# MegaShield.net
KiCad netlist of a schematic drawn in EAGLE
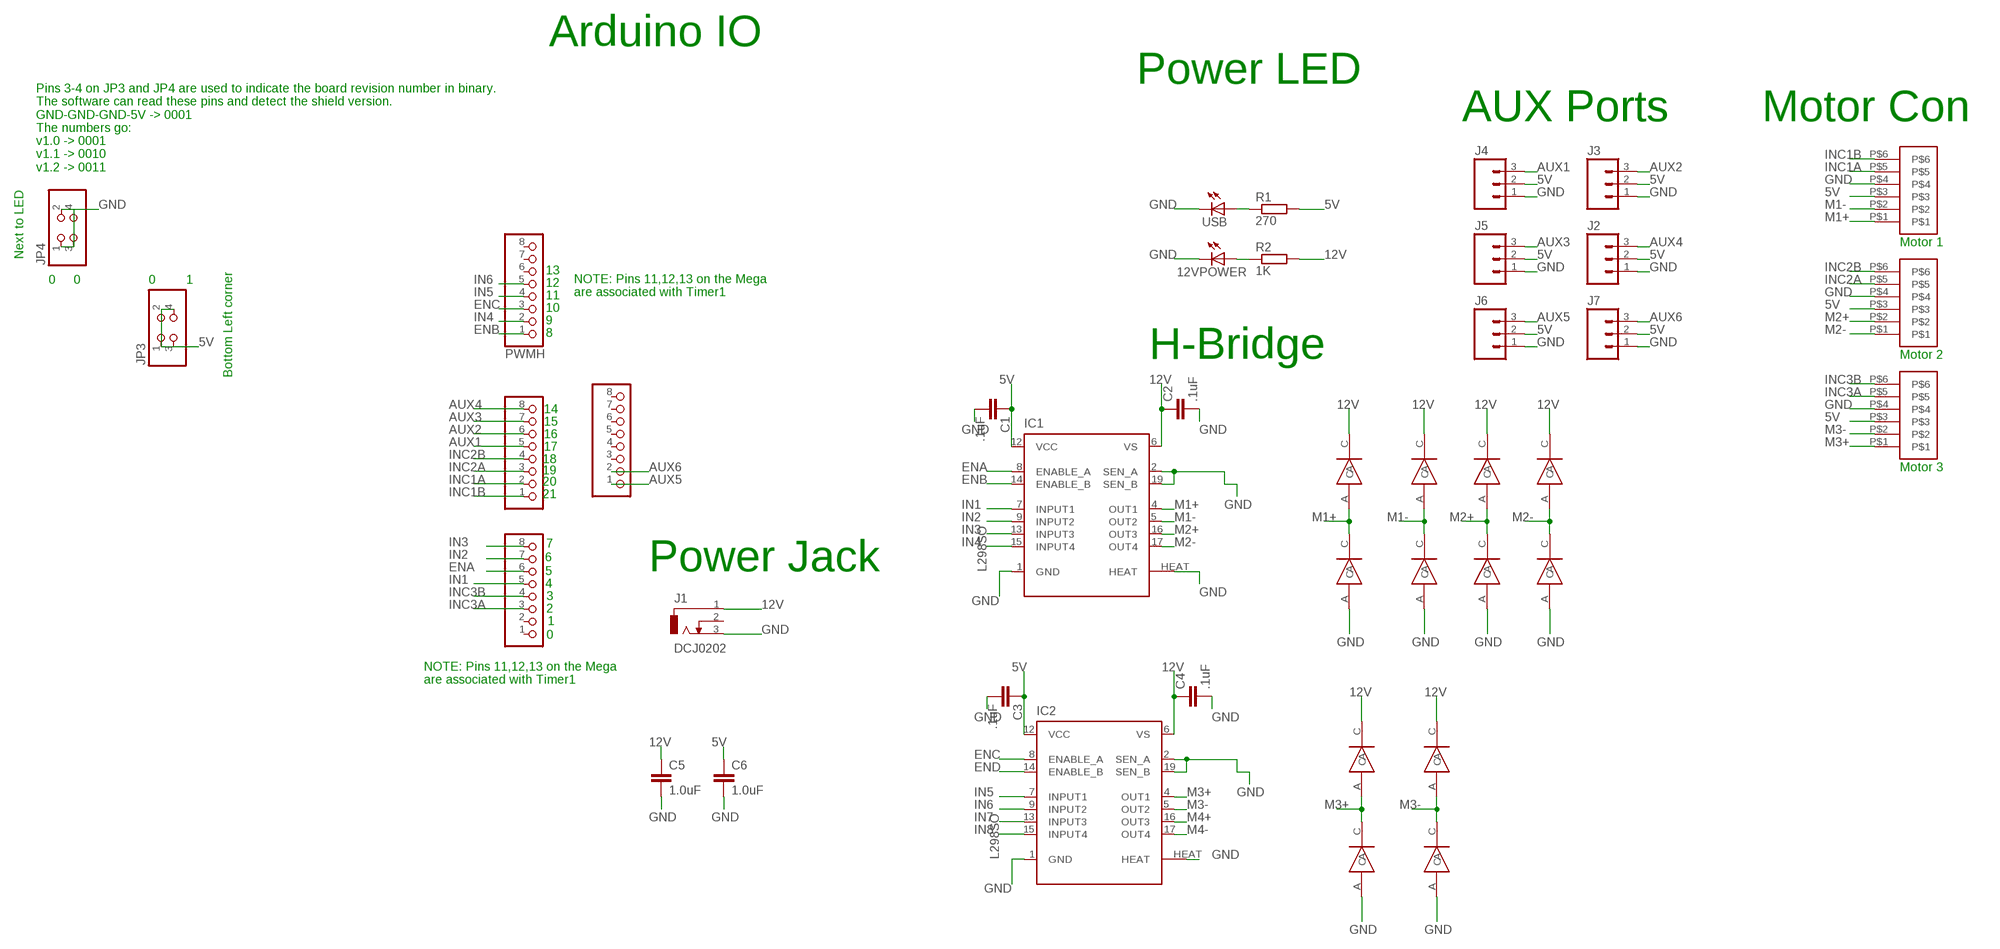
[diagram p0: schematic, sheet 1]

(export (version "E")
  (design (tool "Eeschema 10.0.6"))
  (components
    (comp (ref "12VPOWER")
      (value "LED_E")
      (footprint "eagle-import:LED_1206")
      (libsource (lib "eagle-import") (part "LED_E"))
    )
    (comp (ref "C1")
      (value ".1uF")
      (footprint "eagle-import:C0805")
      (libsource (lib "eagle-import") (part "C"))
    )
    (comp (ref "C2")
      (value ".1uF")
      (footprint "eagle-import:C0805")
      (libsource (lib "eagle-import") (part "C"))
    )
    (comp (ref "C3")
      (value ".1uF")
      (footprint "eagle-import:C0805")
      (libsource (lib "eagle-import") (part "C"))
    )
    (comp (ref "C4")
      (value ".1uF")
      (footprint "eagle-import:C0805")
      (libsource (lib "eagle-import") (part "C"))
    )
    (comp (ref "C5")
      (value "1.0uF")
      (footprint "eagle-import:0805-CAP")
      (libsource (lib "eagle-import") (part "1.0UF-25V-+80/-20(0805){dblquote}"))
    )
    (comp (ref "C6")
      (value "1.0uF")
      (footprint "eagle-import:0805-CAP")
      (libsource (lib "eagle-import") (part "1.0UF-25V-+80/-20(0805){dblquote}"))
    )
    (comp (ref "COMMUNICATION")
      (value "PINHD-1X8")
      (footprint "eagle-import:1X08")
      (libsource (lib "eagle-import") (part "PINHD-1X8"))
    )
    (comp (ref "COMMUNICATION1")
      (value "PINHD-1X8")
      (footprint "eagle-import:1X08")
      (libsource (lib "eagle-import") (part "PINHD-1X8"))
    )
    (comp (ref "IC1")
      (value "L298SO")
      (footprint "eagle-import:POWERSO-20")
      (libsource (lib "eagle-import") (part "L298SO"))
    )
    (comp (ref "IC2")
      (value "L298SO")
      (footprint "eagle-import:POWERSO-20")
      (libsource (lib "eagle-import") (part "L298SO"))
    )
    (comp (ref "J1")
      (value "DCJ0202")
      (footprint "eagle-import:DCJ0202")
      (libsource (lib "eagle-import") (part "DCJ0202"))
    )
    (comp (ref "J2")
      (value "M03LOCK")
      (footprint "eagle-import:1X03_LOCK")
      (libsource (lib "eagle-import") (part "M03LOCK"))
    )
    (comp (ref "J3")
      (value "M03LOCK")
      (footprint "eagle-import:1X03_LOCK")
      (libsource (lib "eagle-import") (part "M03LOCK"))
    )
    (comp (ref "J4")
      (value "M03LOCK")
      (footprint "eagle-import:1X03_LOCK")
      (libsource (lib "eagle-import") (part "M03LOCK"))
    )
    (comp (ref "J5")
      (value "M03LOCK")
      (footprint "eagle-import:1X03_LOCK")
      (libsource (lib "eagle-import") (part "M03LOCK"))
    )
    (comp (ref "J6")
      (value "M03LOCK")
      (footprint "eagle-import:1X03_LOCK")
      (libsource (lib "eagle-import") (part "M03LOCK"))
    )
    (comp (ref "J7")
      (value "M03LOCK")
      (footprint "eagle-import:1X03_LOCK")
      (libsource (lib "eagle-import") (part "M03LOCK"))
    )
    (comp (ref "JP3")
      (value "PINHD-2X2")
      (footprint "eagle-import:2X02")
      (libsource (lib "eagle-import") (part "PINHD-2X2"))
    )
    (comp (ref "JP4")
      (value "PINHD-2X2")
      (footprint "eagle-import:2X02")
      (libsource (lib "eagle-import") (part "PINHD-2X2"))
    )
    (comp (ref "PWMH")
      (value "PINHD-1X8")
      (footprint "eagle-import:1X08")
      (libsource (lib "eagle-import") (part "PINHD-1X8"))
    )
    (comp (ref "PWML")
      (value "PINHD-1X8")
      (footprint "eagle-import:1X08")
      (libsource (lib "eagle-import") (part "PINHD-1X8"))
    )
    (comp (ref "R1")
      (value "270")
      (footprint "eagle-import:R0805")
      (libsource (lib "eagle-import") (part "R"))
    )
    (comp (ref "R2")
      (value "1K")
      (footprint "eagle-import:R0805")
      (libsource (lib "eagle-import") (part "R"))
    )
    (comp (ref "U$1")
      (value "JST-PH-6")
      (footprint "eagle-import:JST-PHR-6-SMD")
      (libsource (lib "eagle-import") (part "JST-PH-6"))
    )
    (comp (ref "U$2")
      (value "MRA4004")
      (footprint "eagle-import:SMA")
      (libsource (lib "eagle-import") (part "MRA4004"))
    )
    (comp (ref "U$3")
      (value "MRA4004")
      (footprint "eagle-import:SMA")
      (libsource (lib "eagle-import") (part "MRA4004"))
    )
    (comp (ref "U$4")
      (value "MRA4004")
      (footprint "eagle-import:SMA")
      (libsource (lib "eagle-import") (part "MRA4004"))
    )
    (comp (ref "U$5")
      (value "MRA4004")
      (footprint "eagle-import:SMA")
      (libsource (lib "eagle-import") (part "MRA4004"))
    )
    (comp (ref "U$6")
      (value "MRA4004")
      (footprint "eagle-import:SMA")
      (libsource (lib "eagle-import") (part "MRA4004"))
    )
    (comp (ref "U$7")
      (value "MRA4004")
      (footprint "eagle-import:SMA")
      (libsource (lib "eagle-import") (part "MRA4004"))
    )
    (comp (ref "U$8")
      (value "MRA4004")
      (footprint "eagle-import:SMA")
      (libsource (lib "eagle-import") (part "MRA4004"))
    )
    (comp (ref "U$9")
      (value "MRA4004")
      (footprint "eagle-import:SMA")
      (libsource (lib "eagle-import") (part "MRA4004"))
    )
    (comp (ref "U$10")
      (value "MRA4004")
      (footprint "eagle-import:SMA")
      (libsource (lib "eagle-import") (part "MRA4004"))
    )
    (comp (ref "U$11")
      (value "MRA4004")
      (footprint "eagle-import:SMA")
      (libsource (lib "eagle-import") (part "MRA4004"))
    )
    (comp (ref "U$12")
      (value "JST-PH-6")
      (footprint "eagle-import:JST-PHR-6-SMD")
      (libsource (lib "eagle-import") (part "JST-PH-6"))
    )
    (comp (ref "U$13")
      (value "MRA4004")
      (footprint "eagle-import:SMA")
      (libsource (lib "eagle-import") (part "MRA4004"))
    )
    (comp (ref "U$14")
      (value "MRA4004")
      (footprint "eagle-import:SMA")
      (libsource (lib "eagle-import") (part "MRA4004"))
    )
    (comp (ref "U$20")
      (value "JST-PH-6")
      (footprint "eagle-import:JST-PHR-6-SMD")
      (libsource (lib "eagle-import") (part "JST-PH-6"))
    )
    (comp (ref "USB")
      (value "LED_E")
      (footprint "eagle-import:LED_1206")
      (libsource (lib "eagle-import") (part "LED_E"))
    )
  )
  (nets
    (net (code "1") (name "/5V") (class "Default")
      (node (ref "C1") (pin "1") (pinfunction "1_1") (pintype "passive"))
      (node (ref "C3") (pin "1") (pinfunction "1_1") (pintype "passive"))
      (node (ref "C6") (pin "1") (pinfunction "1_1") (pintype "passive"))
      (node (ref "IC1") (pin "12") (pinfunction "VCC_12") (pintype "power_in"))
      (node (ref "IC2") (pin "12") (pinfunction "VCC_12") (pintype "power_in"))
      (node (ref "J2") (pin "2") (pinfunction "2_2") (pintype "passive"))
      (node (ref "J3") (pin "2") (pinfunction "2_2") (pintype "passive"))
      (node (ref "J4") (pin "2") (pinfunction "2_2") (pintype "passive"))
      (node (ref "J5") (pin "2") (pinfunction "2_2") (pintype "passive"))
      (node (ref "J6") (pin "2") (pinfunction "2_2") (pintype "passive"))
      (node (ref "J7") (pin "2") (pinfunction "2_2") (pintype "passive"))
      (node (ref "JP3") (pin "1") (pinfunction "1_1") (pintype "passive"))
      (node (ref "JP3") (pin "2") (pinfunction "2_2") (pintype "passive"))
      (node (ref "JP3") (pin "3") (pinfunction "3_3") (pintype "passive"))
      (node (ref "JP3") (pin "4") (pinfunction "4_4") (pintype "passive"))
      (node (ref "R1") (pin "2") (pinfunction "2_2") (pintype "passive"))
      (node (ref "U$1") (pin "P$3") (pinfunction "P$3_P$3") (pintype "bidirectional"))
      (node (ref "U$12") (pin "P$3") (pinfunction "P$3_P$3") (pintype "bidirectional"))
      (node (ref "U$20") (pin "P$3") (pinfunction "P$3_P$3") (pintype "bidirectional"))
    )
    (net (code "2") (name "/12V") (class "Default")
      (node (ref "C2") (pin "1") (pinfunction "1_1") (pintype "passive"))
      (node (ref "C4") (pin "1") (pinfunction "1_1") (pintype "passive"))
      (node (ref "C5") (pin "1") (pinfunction "1_1") (pintype "passive"))
      (node (ref "IC1") (pin "6") (pinfunction "VS_6") (pintype "power_in"))
      (node (ref "IC2") (pin "6") (pinfunction "VS_6") (pintype "power_in"))
      (node (ref "J1") (pin "1") (pinfunction "1_1") (pintype "passive"))
      (node (ref "R2") (pin "2") (pinfunction "2_2") (pintype "passive"))
      (node (ref "U$13") (pin "C") (pinfunction "C_C") (pintype "bidirectional"))
      (node (ref "U$2") (pin "C") (pinfunction "C_C") (pintype "bidirectional"))
      (node (ref "U$3") (pin "C") (pinfunction "C_C") (pintype "bidirectional"))
      (node (ref "U$5") (pin "C") (pinfunction "C_C") (pintype "bidirectional"))
      (node (ref "U$7") (pin "C") (pinfunction "C_C") (pintype "bidirectional"))
      (node (ref "U$9") (pin "C") (pinfunction "C_C") (pintype "bidirectional"))
    )
    (net (code "3") (name "/AUX1") (class "Default")
      (node (ref "COMMUNICATION") (pin "5") (pinfunction "5_5") (pintype "passive"))
      (node (ref "J4") (pin "3") (pinfunction "3_3") (pintype "passive"))
    )
    (net (code "4") (name "/AUX2") (class "Default")
      (node (ref "COMMUNICATION") (pin "6") (pinfunction "6_6") (pintype "passive"))
      (node (ref "J3") (pin "3") (pinfunction "3_3") (pintype "passive"))
    )
    (net (code "5") (name "/AUX3") (class "Default")
      (node (ref "COMMUNICATION") (pin "7") (pinfunction "7_7") (pintype "passive"))
      (node (ref "J5") (pin "3") (pinfunction "3_3") (pintype "passive"))
    )
    (net (code "6") (name "/AUX4") (class "Default")
      (node (ref "COMMUNICATION") (pin "8") (pinfunction "8_8") (pintype "passive"))
      (node (ref "J2") (pin "3") (pinfunction "3_3") (pintype "passive"))
    )
    (net (code "7") (name "/AUX5") (class "Default")
      (node (ref "COMMUNICATION1") (pin "1") (pinfunction "1_1") (pintype "passive"))
      (node (ref "J6") (pin "3") (pinfunction "3_3") (pintype "passive"))
    )
    (net (code "8") (name "/AUX6") (class "Default")
      (node (ref "COMMUNICATION1") (pin "2") (pinfunction "2_2") (pintype "passive"))
      (node (ref "J7") (pin "3") (pinfunction "3_3") (pintype "passive"))
    )
    (net (code "9") (name "/ENA") (class "Default")
      (node (ref "IC1") (pin "8") (pinfunction "ENABLE_A_8") (pintype "input"))
      (node (ref "PWML") (pin "6") (pinfunction "6_6") (pintype "passive"))
    )
    (net (code "10") (name "/ENB") (class "Default")
      (node (ref "IC1") (pin "14") (pinfunction "ENABLE_B_14") (pintype "input"))
      (node (ref "PWMH") (pin "1") (pinfunction "1_1") (pintype "passive"))
    )
    (net (code "11") (name "/ENC") (class "Default")
      (node (ref "IC2") (pin "8") (pinfunction "ENABLE_A_8") (pintype "input"))
      (node (ref "PWMH") (pin "3") (pinfunction "3_3") (pintype "passive"))
    )
    (net (code "12") (name "/END") (class "Default")
      (node (ref "IC2") (pin "14") (pinfunction "ENABLE_B_14") (pintype "input"))
    )
    (net (code "13") (name "/GND") (class "Default")
      (node (ref "12VPOWER") (pin "C") (pinfunction "C_C") (pintype "passive"))
      (node (ref "C1") (pin "2") (pinfunction "2_2") (pintype "passive"))
      (node (ref "C2") (pin "2") (pinfunction "2_2") (pintype "passive"))
      (node (ref "C3") (pin "2") (pinfunction "2_2") (pintype "passive"))
      (node (ref "C4") (pin "2") (pinfunction "2_2") (pintype "passive"))
      (node (ref "C5") (pin "2") (pinfunction "2_2") (pintype "passive"))
      (node (ref "C6") (pin "2") (pinfunction "2_2") (pintype "passive"))
      (node (ref "IC1") (pin "1") (pinfunction "GND_1") (pintype "power_in"))
      (node (ref "IC1") (pin "19") (pinfunction "SEN_B_19") (pintype "input"))
      (node (ref "IC1") (pin "2") (pinfunction "SEN_A_2") (pintype "input"))
      (node (ref "IC1") (pin "HEAT") (pinfunction "HEAT_HEAT") (pintype "bidirectional"))
      (node (ref "IC2") (pin "1") (pinfunction "GND_1") (pintype "power_in"))
      (node (ref "IC2") (pin "19") (pinfunction "SEN_B_19") (pintype "input"))
      (node (ref "IC2") (pin "2") (pinfunction "SEN_A_2") (pintype "input"))
      (node (ref "IC2") (pin "HEAT") (pinfunction "HEAT_HEAT") (pintype "bidirectional"))
      (node (ref "J1") (pin "3") (pinfunction "3_3") (pintype "passive"))
      (node (ref "J2") (pin "1") (pinfunction "1_1") (pintype "passive"))
      (node (ref "J3") (pin "1") (pinfunction "1_1") (pintype "passive"))
      (node (ref "J4") (pin "1") (pinfunction "1_1") (pintype "passive"))
      (node (ref "J5") (pin "1") (pinfunction "1_1") (pintype "passive"))
      (node (ref "J6") (pin "1") (pinfunction "1_1") (pintype "passive"))
      (node (ref "J7") (pin "1") (pinfunction "1_1") (pintype "passive"))
      (node (ref "JP4") (pin "1") (pinfunction "1_1") (pintype "passive"))
      (node (ref "JP4") (pin "2") (pinfunction "2_2") (pintype "passive"))
      (node (ref "JP4") (pin "3") (pinfunction "3_3") (pintype "passive"))
      (node (ref "JP4") (pin "4") (pinfunction "4_4") (pintype "passive"))
      (node (ref "U$1") (pin "P$4") (pinfunction "P$4_P$4") (pintype "bidirectional"))
      (node (ref "U$10") (pin "A") (pinfunction "A_A") (pintype "bidirectional"))
      (node (ref "U$11") (pin "A") (pinfunction "A_A") (pintype "bidirectional"))
      (node (ref "U$12") (pin "P$4") (pinfunction "P$4_P$4") (pintype "bidirectional"))
      (node (ref "U$14") (pin "A") (pinfunction "A_A") (pintype "bidirectional"))
      (node (ref "U$20") (pin "P$4") (pinfunction "P$4_P$4") (pintype "bidirectional"))
      (node (ref "U$4") (pin "A") (pinfunction "A_A") (pintype "bidirectional"))
      (node (ref "U$6") (pin "A") (pinfunction "A_A") (pintype "bidirectional"))
      (node (ref "U$8") (pin "A") (pinfunction "A_A") (pintype "bidirectional"))
      (node (ref "USB") (pin "C") (pinfunction "C_C") (pintype "passive"))
    )
    (net (code "14") (name "/IN1") (class "Default")
      (node (ref "IC1") (pin "7") (pinfunction "INPUT1_7") (pintype "input"))
      (node (ref "PWML") (pin "5") (pinfunction "5_5") (pintype "passive"))
    )
    (net (code "15") (name "/IN2") (class "Default")
      (node (ref "IC1") (pin "9") (pinfunction "INPUT2_9") (pintype "input"))
      (node (ref "PWML") (pin "7") (pinfunction "7_7") (pintype "passive"))
    )
    (net (code "16") (name "/IN3") (class "Default")
      (node (ref "IC1") (pin "13") (pinfunction "INPUT3_13") (pintype "input"))
      (node (ref "PWML") (pin "8") (pinfunction "8_8") (pintype "passive"))
    )
    (net (code "17") (name "/IN4") (class "Default")
      (node (ref "IC1") (pin "15") (pinfunction "INPUT4_15") (pintype "input"))
      (node (ref "PWMH") (pin "2") (pinfunction "2_2") (pintype "passive"))
    )
    (net (code "18") (name "/IN5") (class "Default")
      (node (ref "IC2") (pin "7") (pinfunction "INPUT1_7") (pintype "input"))
      (node (ref "PWMH") (pin "4") (pinfunction "4_4") (pintype "passive"))
    )
    (net (code "19") (name "/IN6") (class "Default")
      (node (ref "IC2") (pin "9") (pinfunction "INPUT2_9") (pintype "input"))
      (node (ref "PWMH") (pin "5") (pinfunction "5_5") (pintype "passive"))
    )
    (net (code "20") (name "/IN7") (class "Default")
      (node (ref "IC2") (pin "13") (pinfunction "INPUT3_13") (pintype "input"))
    )
    (net (code "21") (name "/IN8") (class "Default")
      (node (ref "IC2") (pin "15") (pinfunction "INPUT4_15") (pintype "input"))
    )
    (net (code "22") (name "/INC1A") (class "Default")
      (node (ref "COMMUNICATION") (pin "2") (pinfunction "2_2") (pintype "passive"))
      (node (ref "U$1") (pin "P$5") (pinfunction "P$5_P$5") (pintype "bidirectional"))
    )
    (net (code "23") (name "/INC1B") (class "Default")
      (node (ref "COMMUNICATION") (pin "1") (pinfunction "1_1") (pintype "passive"))
      (node (ref "U$1") (pin "P$6") (pinfunction "P$6_P$6") (pintype "bidirectional"))
    )
    (net (code "24") (name "/INC2A") (class "Default")
      (node (ref "COMMUNICATION") (pin "3") (pinfunction "3_3") (pintype "passive"))
      (node (ref "U$12") (pin "P$5") (pinfunction "P$5_P$5") (pintype "bidirectional"))
    )
    (net (code "25") (name "/INC2B") (class "Default")
      (node (ref "COMMUNICATION") (pin "4") (pinfunction "4_4") (pintype "passive"))
      (node (ref "U$12") (pin "P$6") (pinfunction "P$6_P$6") (pintype "bidirectional"))
    )
    (net (code "26") (name "/INC3A") (class "Default")
      (node (ref "PWML") (pin "3") (pinfunction "3_3") (pintype "passive"))
      (node (ref "U$20") (pin "P$5") (pinfunction "P$5_P$5") (pintype "bidirectional"))
    )
    (net (code "27") (name "/INC3B") (class "Default")
      (node (ref "PWML") (pin "4") (pinfunction "4_4") (pintype "passive"))
      (node (ref "U$20") (pin "P$6") (pinfunction "P$6_P$6") (pintype "bidirectional"))
    )
    (net (code "28") (name "/M1+") (class "Default")
      (node (ref "IC1") (pin "4") (pinfunction "OUT1_4") (pintype "output"))
      (node (ref "U$1") (pin "P$1") (pinfunction "P$1_P$1") (pintype "bidirectional"))
      (node (ref "U$3") (pin "A") (pinfunction "A_A") (pintype "bidirectional"))
      (node (ref "U$4") (pin "C") (pinfunction "C_C") (pintype "bidirectional"))
    )
    (net (code "29") (name "/M1-") (class "Default")
      (node (ref "IC1") (pin "5") (pinfunction "OUT2_5") (pintype "output"))
      (node (ref "U$1") (pin "P$2") (pinfunction "P$2_P$2") (pintype "bidirectional"))
      (node (ref "U$5") (pin "A") (pinfunction "A_A") (pintype "bidirectional"))
      (node (ref "U$6") (pin "C") (pinfunction "C_C") (pintype "bidirectional"))
    )
    (net (code "30") (name "/M2+") (class "Default")
      (node (ref "IC1") (pin "16") (pinfunction "OUT3_16") (pintype "output"))
      (node (ref "U$12") (pin "P$2") (pinfunction "P$2_P$2") (pintype "bidirectional"))
      (node (ref "U$7") (pin "A") (pinfunction "A_A") (pintype "bidirectional"))
      (node (ref "U$8") (pin "C") (pinfunction "C_C") (pintype "bidirectional"))
    )
    (net (code "31") (name "/M2-") (class "Default")
      (node (ref "IC1") (pin "17") (pinfunction "OUT4_17") (pintype "output"))
      (node (ref "U$10") (pin "C") (pinfunction "C_C") (pintype "bidirectional"))
      (node (ref "U$12") (pin "P$1") (pinfunction "P$1_P$1") (pintype "bidirectional"))
      (node (ref "U$9") (pin "A") (pinfunction "A_A") (pintype "bidirectional"))
    )
    (net (code "32") (name "/M3+") (class "Default")
      (node (ref "IC2") (pin "4") (pinfunction "OUT1_4") (pintype "output"))
      (node (ref "U$11") (pin "C") (pinfunction "C_C") (pintype "bidirectional"))
      (node (ref "U$2") (pin "A") (pinfunction "A_A") (pintype "bidirectional"))
      (node (ref "U$20") (pin "P$1") (pinfunction "P$1_P$1") (pintype "bidirectional"))
    )
    (net (code "33") (name "/M3-") (class "Default")
      (node (ref "IC2") (pin "5") (pinfunction "OUT2_5") (pintype "output"))
      (node (ref "U$13") (pin "A") (pinfunction "A_A") (pintype "bidirectional"))
      (node (ref "U$14") (pin "C") (pinfunction "C_C") (pintype "bidirectional"))
      (node (ref "U$20") (pin "P$2") (pinfunction "P$2_P$2") (pintype "bidirectional"))
    )
    (net (code "34") (name "/M4+") (class "Default")
      (node (ref "IC2") (pin "16") (pinfunction "OUT3_16") (pintype "output"))
    )
    (net (code "35") (name "/M4-") (class "Default")
      (node (ref "IC2") (pin "17") (pinfunction "OUT4_17") (pintype "output"))
    )
    (net (code "36") (name "Net-(12VPOWER-PadA)") (class "Default")
      (node (ref "12VPOWER") (pin "A") (pinfunction "A_A") (pintype "passive"))
      (node (ref "R2") (pin "1") (pinfunction "1_1") (pintype "passive"))
    )
    (net (code "37") (name "Net-(R1-Pad1)") (class "Default")
      (node (ref "R1") (pin "1") (pinfunction "1_1") (pintype "passive"))
      (node (ref "USB") (pin "A") (pinfunction "A_A") (pintype "passive"))
    )
    (net (code "38") (name "unconnected-(COMMUNICATION1-Pad3)") (class "Default")
      (node (ref "COMMUNICATION1") (pin "3") (pinfunction "3_3") (pintype "passive"))
    )
    (net (code "39") (name "unconnected-(COMMUNICATION1-Pad4)") (class "Default")
      (node (ref "COMMUNICATION1") (pin "4") (pinfunction "4_4") (pintype "passive"))
    )
    (net (code "40") (name "unconnected-(COMMUNICATION1-Pad5)") (class "Default")
      (node (ref "COMMUNICATION1") (pin "5") (pinfunction "5_5") (pintype "passive"))
    )
    (net (code "41") (name "unconnected-(COMMUNICATION1-Pad6)") (class "Default")
      (node (ref "COMMUNICATION1") (pin "6") (pinfunction "6_6") (pintype "passive"))
    )
    (net (code "42") (name "unconnected-(COMMUNICATION1-Pad7)") (class "Default")
      (node (ref "COMMUNICATION1") (pin "7") (pinfunction "7_7") (pintype "passive"))
    )
    (net (code "43") (name "unconnected-(COMMUNICATION1-Pad8)") (class "Default")
      (node (ref "COMMUNICATION1") (pin "8") (pinfunction "8_8") (pintype "passive"))
    )
    (net (code "44") (name "unconnected-(J1-Pad2)") (class "Default")
      (node (ref "J1") (pin "2") (pinfunction "2_2") (pintype "passive"))
    )
    (net (code "45") (name "unconnected-(PWMH-Pad6)") (class "Default")
      (node (ref "PWMH") (pin "6") (pinfunction "6_6") (pintype "passive"))
    )
    (net (code "46") (name "unconnected-(PWMH-Pad7)") (class "Default")
      (node (ref "PWMH") (pin "7") (pinfunction "7_7") (pintype "passive"))
    )
    (net (code "47") (name "unconnected-(PWMH-Pad8)") (class "Default")
      (node (ref "PWMH") (pin "8") (pinfunction "8_8") (pintype "passive"))
    )
    (net (code "48") (name "unconnected-(PWML-Pad1)") (class "Default")
      (node (ref "PWML") (pin "1") (pinfunction "1_1") (pintype "passive"))
    )
    (net (code "49") (name "unconnected-(PWML-Pad2)") (class "Default")
      (node (ref "PWML") (pin "2") (pinfunction "2_2") (pintype "passive"))
    )
  )
)
